# LG_TRACKER_Microcontroller.net
KiCad netlist of a schematic drawn in Altium Designer
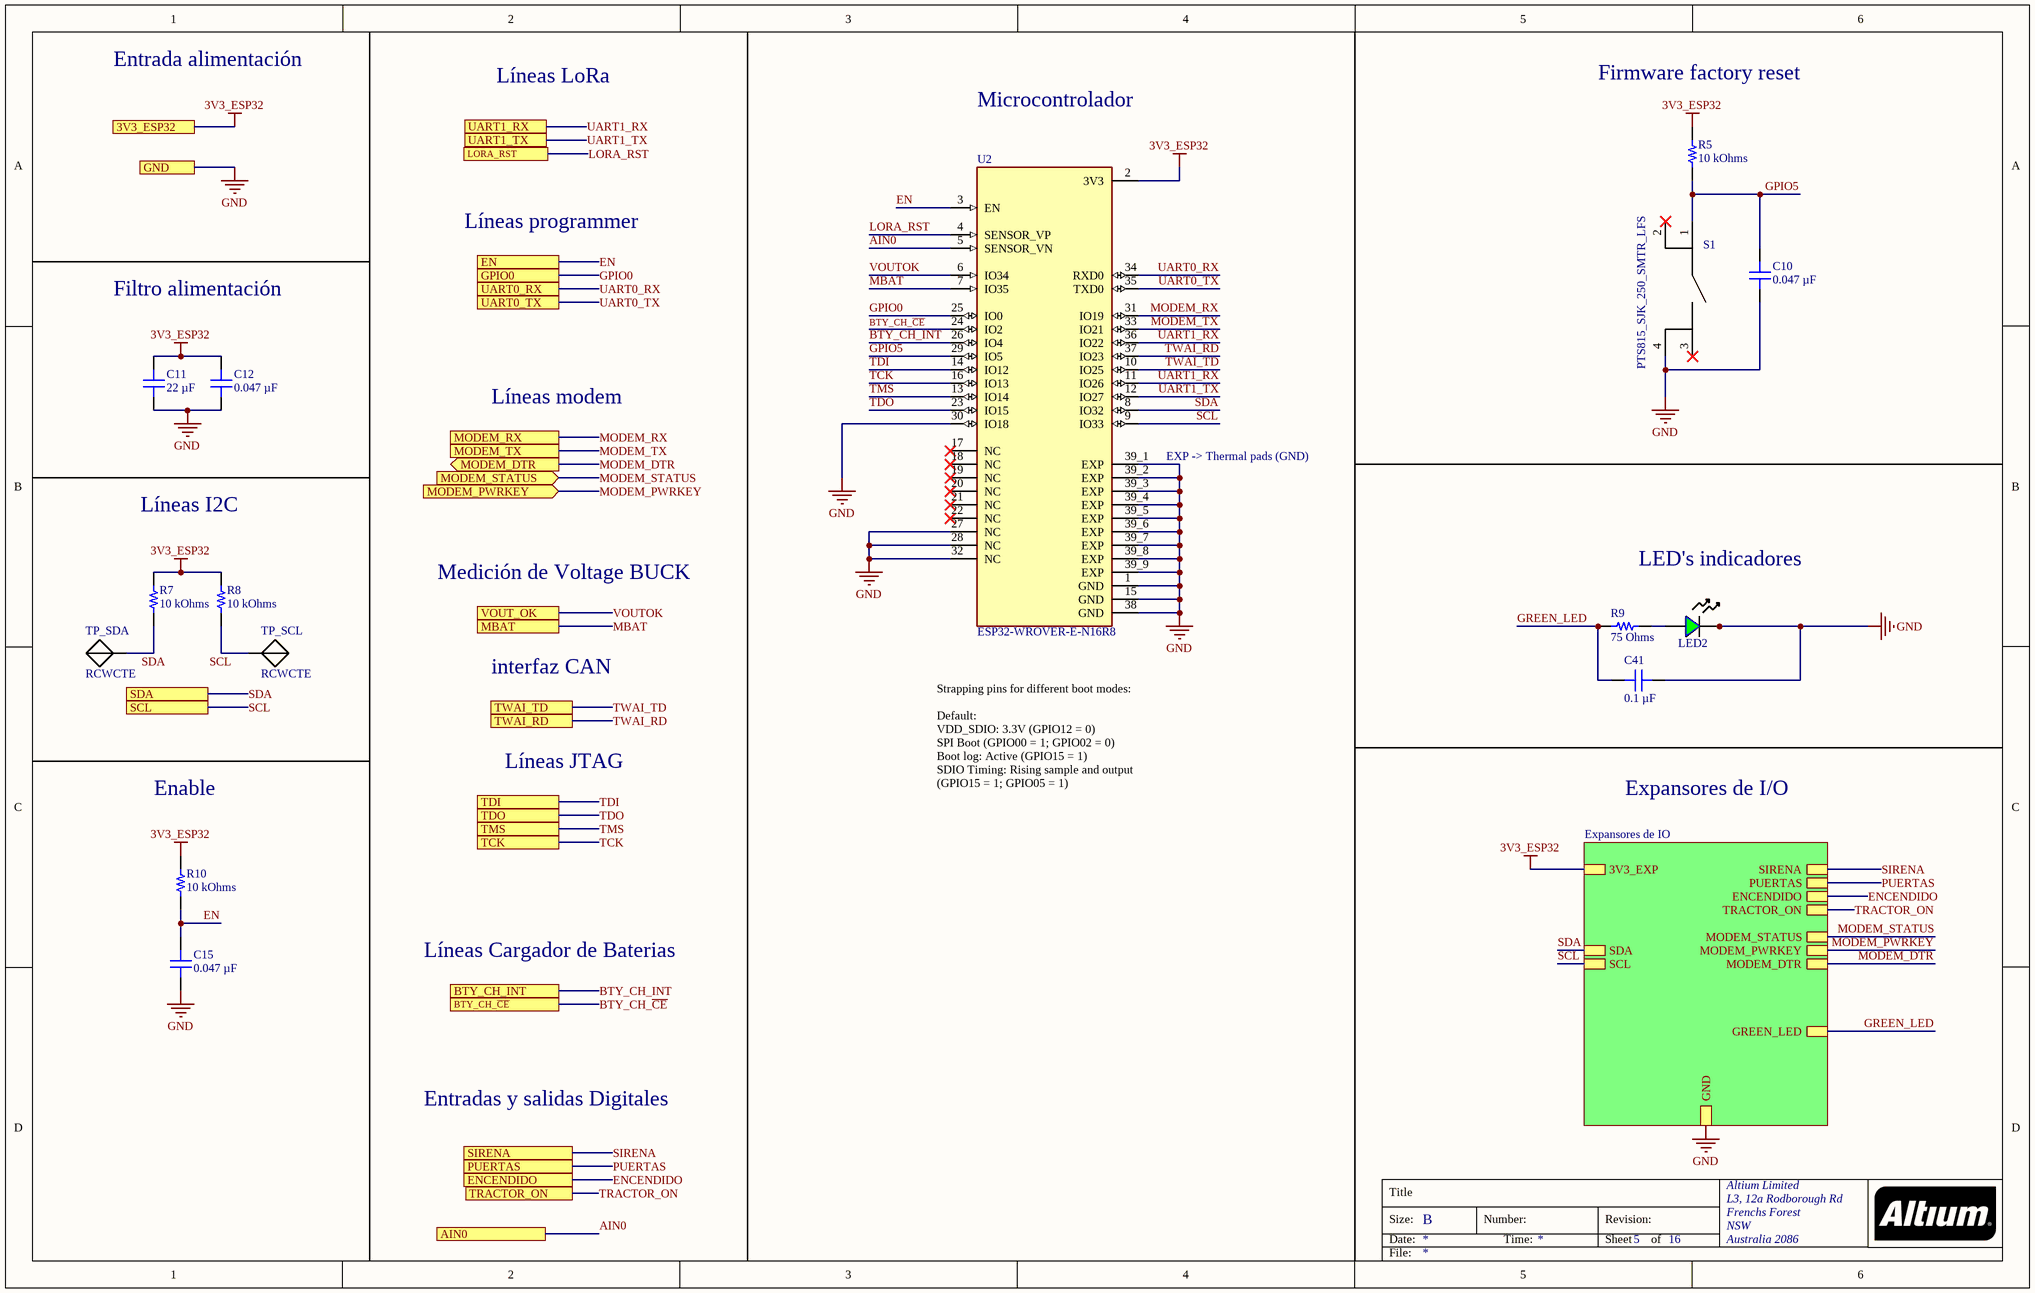
[diagram p0: LG_TRACKER_Microcontroller.SchDoc]

(export (version "E")
  (design (tool "Eeschema 10.0.6"))
  (components
    (comp (ref "C10")
      (value "0.047 µF")
      (footprint "CAP 0603_1608")
      (description "CAP CER 0.047UF 100V X7R 0603")
      (fields (field (name "PART NUMBER") "885012206118") (field (name "MANUFACTURER") "Würth Elektronik"))
      (libsource (lib "Celestial Altium Library - altium_library") (part "Capacitor"))
    )
    (comp (ref "C11")
      (value "22 µF")
      (footprint "CAP 0805_2012")
      (description "CAP CER 22UF 16V X5R 0805")
      (fields
        (field (name "PART NUMBER") "CL21A226MOCLRNC")
        (field (name "MANUFACTURER") "Samsung Electro-Mechanics")
      )
      (libsource (lib "Celestial Altium Library - altium_library") (part "Capacitor"))
    )
    (comp (ref "C12")
      (value "0.047 µF")
      (footprint "CAP 0603_1608")
      (description "CAP CER 0.047UF 100V X7R 0603")
      (fields (field (name "PART NUMBER") "885012206118") (field (name "MANUFACTURER") "Würth Elektronik"))
      (libsource (lib "Celestial Altium Library - altium_library") (part "Capacitor"))
    )
    (comp (ref "C15")
      (value "0.047 µF")
      (footprint "CAP 0603_1608")
      (description "CAP CER 0.047UF 100V X7R 0603")
      (fields (field (name "PART NUMBER") "885012206118") (field (name "MANUFACTURER") "Würth Elektronik"))
      (libsource (lib "Celestial Altium Library - altium_library") (part "Capacitor"))
    )
    (comp (ref "C41")
      (value "0.1 µF")
      (footprint "CAP 0402_1005")
      (description "CAP CER 0.1UF 50V X5R 0402")
      (fields
        (field (name "PART NUMBER") "CGA2B3X5R1H104M050BB")
        (field (name "CAPACITANCE") "0.1 µF")
        (field (name "MANUFACTURER") "TDK Corporation")
      )
      (libsource (lib "Celestial Altium Library - altium_library") (part "Capacitor"))
    )
    (comp (ref "LED2")
      (value "LTST-C170GKT")
      (footprint "0805 SMD - LED")
      (description "LED verde SMD (0805)")
      (fields (field (name "COPYRIGHT") "Copyright (C) 2023 Ultra Librarian. All rights reserved."))
      (libsource (lib "DIN_DC_Base_Board_components_SCH_footprints") (part "LTST-C170GKT"))
    )
    (comp (ref "R5")
      (value "10 kOhms")
      (footprint "RES 0603_1608")
      (description "RES 10K OHM 1% 1/10W 0603")
      (fields (field (name "PART NUMBER") "RC0603FR-0710KL") (field (name "MANUFACTURER") "Yageo"))
      (libsource (lib "Celestial Altium Library - altium_library") (part "Resistor"))
    )
    (comp (ref "R7")
      (value "10 kOhms")
      (footprint "RES 0603_1608")
      (description "RES 10K OHM 1% 1/10W 0603")
      (fields (field (name "PART NUMBER") "RC0603FR-0710KL") (field (name "MANUFACTURER") "Yageo"))
      (libsource (lib "Celestial Altium Library - altium_library") (part "Resistor"))
    )
    (comp (ref "R8")
      (value "10 kOhms")
      (footprint "RES 0603_1608")
      (description "RES 10K OHM 1% 1/10W 0603")
      (fields (field (name "PART NUMBER") "RC0603FR-0710KL") (field (name "MANUFACTURER") "Yageo"))
      (libsource (lib "Celestial Altium Library - altium_library") (part "Resistor"))
    )
    (comp (ref "R9")
      (value "75 Ohms")
      (footprint "RES 0402_1005")
      (description "RES 75 OHM 1% 1/16W 0402")
      (fields (field (name "PART NUMBER") "CRCW040275R0FKEDC") (field (name "MANUFACTURER") "Vishay Dale"))
      (libsource (lib "Celestial Altium Library - altium_library") (part "Resistor"))
    )
    (comp (ref "R10")
      (value "10 kOhms")
      (footprint "RES 0603_1608")
      (description "RES 10K OHM 1% 1/10W 0603")
      (fields (field (name "PART NUMBER") "RC0603FR-0710KL") (field (name "MANUFACTURER") "Yageo"))
      (libsource (lib "Celestial Altium Library - altium_library") (part "Resistor"))
    )
    (comp (ref "S1")
      (value "PTS815_SJK_250_SMTR_LFS")
      (footprint "PTS815SJK250SMTRLFS")
      (description "Switch")
      (fields
        (field (name "MANUFACTURER_PART_NUMBER") "PTS815 SJK 250 SMTR LFS")
        (field (name "MOUSER PART NUMBER") "611-PTS815SJK250SMTR")
      )
      (libsource (lib "DIN_DC_Base_Board_components") (part "PTS815_SJK_250_SMTR_LFS"))
    )
    (comp (ref "TP_SCL")
      (value "RCWCTE")
      (footprint "RCWCTE")
      (description "- PC Test Point - - Plating Surface Mount Mounting Type")
      (fields (field (name "MF") "KOA Speer") (field (name "DIGI-KEY_PART_NUMBER") "2019-RCWCTETR-ND"))
      (libsource (lib "DIN_DC_Base_Board_components") (part "RCWCTE"))
    )
    (comp (ref "TP_SDA")
      (value "RCWCTE")
      (footprint "RCWCTE")
      (description "- PC Test Point - - Plating Surface Mount Mounting Type")
      (fields (field (name "MF") "KOA Speer") (field (name "DIGI-KEY_PART_NUMBER") "2019-RCWCTETR-ND"))
      (libsource (lib "DIN_DC_Base_Board_components") (part "RCWCTE"))
    )
    (comp (ref "U2")
      (value "ESP32-WROVER-E-N16R8")
      (footprint "ESP32-WROVER-E-N16R8")
      (libsource (lib "DIN_DC_Base_Board_components_SCH_footprints") (part "ESP32-WROVER-E-N16R8"))
    )
  )
  (nets
    (net (code "1") (name "/AIN0") (class "Default")
      (node (ref "U2") (pin "5") (pinfunction "SENSOR_VN_5") (pintype "input"))
    )
    (net (code "2") (name "/BTY_CH_INT") (class "Default")
      (node (ref "U2") (pin "26") (pinfunction "IO4_26") (pintype "bidirectional"))
    )
    (net (code "3") (name "/BTY_CH_~{CE}") (class "Default")
      (node (ref "U2") (pin "24") (pinfunction "IO2_24") (pintype "bidirectional"))
    )
    (net (code "4") (name "/EN") (class "Default")
      (node (ref "C15") (pin "2") (pinfunction "2_2") (pintype "passive"))
      (node (ref "R10") (pin "1") (pinfunction "1_1") (pintype "passive"))
      (node (ref "U2") (pin "3") (pinfunction "EN_3") (pintype "input"))
    )
    (net (code "6") (name "/GPIO0") (class "Default")
      (node (ref "U2") (pin "25") (pinfunction "IO0_25") (pintype "bidirectional"))
    )
    (net (code "7") (name "/GPIO5") (class "Default")
      (node (ref "C10") (pin "2") (pinfunction "2_2") (pintype "passive"))
      (node (ref "R5") (pin "1") (pinfunction "1_1") (pintype "passive"))
      (node (ref "S1") (pin "1") (pinfunction "COM_1_1") (pintype "passive"))
      (node (ref "U2") (pin "29") (pinfunction "IO5_29") (pintype "bidirectional"))
    )
    (net (code "8") (name "/GREEN_LED") (class "Default")
      (node (ref "C41") (pin "2") (pinfunction "2_2") (pintype "passive"))
      (node (ref "R9") (pin "1") (pinfunction "1_1") (pintype "passive"))
    )
    (net (code "9") (name "/LORA_RST") (class "Default")
      (node (ref "U2") (pin "4") (pinfunction "SENSOR_VP_4") (pintype "input"))
    )
    (net (code "10") (name "/MBAT") (class "Default")
      (node (ref "U2") (pin "7") (pinfunction "IO35_7") (pintype "input"))
    )
    (net (code "13") (name "/MODEM_RX") (class "Default")
      (node (ref "U2") (pin "31") (pinfunction "IO19_31") (pintype "bidirectional"))
    )
    (net (code "15") (name "/MODEM_TX") (class "Default")
      (node (ref "U2") (pin "33") (pinfunction "IO21_33") (pintype "bidirectional"))
    )
    (net (code "17") (name "/SCL") (class "Default")
      (node (ref "R8") (pin "1") (pinfunction "1_1") (pintype "passive"))
      (node (ref "TP_SCL") (pin "1") (pinfunction "TP_1") (pintype "passive"))
      (node (ref "U2") (pin "9") (pinfunction "IO33_9") (pintype "bidirectional"))
    )
    (net (code "18") (name "/SDA") (class "Default")
      (node (ref "R7") (pin "1") (pinfunction "1_1") (pintype "passive"))
      (node (ref "TP_SDA") (pin "1") (pinfunction "TP_1") (pintype "passive"))
      (node (ref "U2") (pin "8") (pinfunction "IO32_8") (pintype "bidirectional"))
    )
    (net (code "20") (name "/TCK") (class "Default")
      (node (ref "U2") (pin "16") (pinfunction "IO13_16") (pintype "bidirectional"))
    )
    (net (code "21") (name "/TDI") (class "Default")
      (node (ref "U2") (pin "14") (pinfunction "IO12_14") (pintype "bidirectional"))
    )
    (net (code "22") (name "/TDO") (class "Default")
      (node (ref "U2") (pin "23") (pinfunction "IO15_23") (pintype "bidirectional"))
    )
    (net (code "23") (name "/TMS") (class "Default")
      (node (ref "U2") (pin "13") (pinfunction "IO14_13") (pintype "bidirectional"))
    )
    (net (code "25") (name "/TWAI_RD") (class "Default")
      (node (ref "U2") (pin "37") (pinfunction "IO23_37") (pintype "bidirectional"))
    )
    (net (code "26") (name "/TWAI_TD") (class "Default")
      (node (ref "U2") (pin "10") (pinfunction "IO25_10") (pintype "bidirectional"))
    )
    (net (code "27") (name "/UART0_RX") (class "Default")
      (node (ref "U2") (pin "34") (pinfunction "RXD0_34") (pintype "bidirectional"))
    )
    (net (code "28") (name "/UART0_TX") (class "Default")
      (node (ref "U2") (pin "35") (pinfunction "TXD0_35") (pintype "bidirectional"))
    )
    (net (code "29") (name "/UART1_RX") (class "Default")
      (node (ref "U2") (pin "11") (pinfunction "IO26_11") (pintype "bidirectional"))
      (node (ref "U2") (pin "36") (pinfunction "IO22_36") (pintype "bidirectional"))
    )
    (net (code "30") (name "/UART1_TX") (class "Default")
      (node (ref "U2") (pin "12") (pinfunction "IO27_12") (pintype "bidirectional"))
    )
    (net (code "31") (name "/VOUTOK") (class "Default")
      (node (ref "U2") (pin "6") (pinfunction "IO34_6") (pintype "input"))
    )
    (net (code "32") (name "3V3_ESP32") (class "Default")
      (node (ref "C11") (pin "2") (pinfunction "2_2") (pintype "passive"))
      (node (ref "C12") (pin "2") (pinfunction "2_2") (pintype "passive"))
      (node (ref "R10") (pin "2") (pinfunction "2_2") (pintype "passive"))
      (node (ref "R5") (pin "2") (pinfunction "2_2") (pintype "passive"))
      (node (ref "R7") (pin "2") (pinfunction "2_2") (pintype "passive"))
      (node (ref "R8") (pin "2") (pinfunction "2_2") (pintype "passive"))
      (node (ref "U2") (pin "2") (pinfunction "3V3_2") (pintype "power_in"))
    )
    (net (code "33") (name "GND") (class "Default")
      (node (ref "C10") (pin "1") (pinfunction "1_1") (pintype "passive"))
      (node (ref "C11") (pin "1") (pinfunction "1_1") (pintype "passive"))
      (node (ref "C12") (pin "1") (pinfunction "1_1") (pintype "passive"))
      (node (ref "C15") (pin "1") (pinfunction "1_1") (pintype "passive"))
      (node (ref "C41") (pin "1") (pinfunction "1_1") (pintype "passive"))
      (node (ref "LED2") (pin "K") (pinfunction "CATHODE_K") (pintype "passive"))
      (node (ref "S1") (pin "4") (pinfunction "N.O._2_4") (pintype "passive"))
      (node (ref "U2") (pin "1") (pinfunction "GND_1") (pintype "power_in"))
      (node (ref "U2") (pin "15") (pinfunction "GND_15") (pintype "power_in"))
      (node (ref "U2") (pin "27") (pinfunction "NC_27") (pintype "passive"))
      (node (ref "U2") (pin "28") (pinfunction "NC_28") (pintype "passive"))
      (node (ref "U2") (pin "30") (pinfunction "IO18_30") (pintype "bidirectional"))
      (node (ref "U2") (pin "32") (pinfunction "NC_32") (pintype "passive"))
      (node (ref "U2") (pin "38") (pinfunction "GND_38") (pintype "power_in"))
      (node (ref "U2") (pin "39_1") (pinfunction "EXP_39_1") (pintype "power_in"))
      (node (ref "U2") (pin "39_2") (pinfunction "EXP_39_2") (pintype "power_in"))
      (node (ref "U2") (pin "39_3") (pinfunction "EXP_39_3") (pintype "power_in"))
      (node (ref "U2") (pin "39_4") (pinfunction "EXP_39_4") (pintype "power_in"))
      (node (ref "U2") (pin "39_5") (pinfunction "EXP_39_5") (pintype "power_in"))
      (node (ref "U2") (pin "39_6") (pinfunction "EXP_39_6") (pintype "power_in"))
      (node (ref "U2") (pin "39_7") (pinfunction "EXP_39_7") (pintype "power_in"))
      (node (ref "U2") (pin "39_8") (pinfunction "EXP_39_8") (pintype "power_in"))
      (node (ref "U2") (pin "39_9") (pinfunction "EXP_39_9") (pintype "power_in"))
    )
    (net (code "34") (name "Net-(LED2-ANODE)") (class "Default")
      (node (ref "LED2") (pin "A") (pinfunction "ANODE_A") (pintype "passive"))
      (node (ref "R9") (pin "2") (pinfunction "2_2") (pintype "passive"))
    )
    (net (code "35") (name "unconnected-(S1-COM_2-Pad2)") (class "Default")
      (node (ref "S1") (pin "2") (pinfunction "COM_2_2") (pintype "passive+no_connect"))
    )
    (net (code "36") (name "unconnected-(S1-N.O._1-Pad3)") (class "Default")
      (node (ref "S1") (pin "3") (pinfunction "N.O._1_3") (pintype "passive+no_connect"))
    )
    (net (code "37") (name "unconnected-(U2-NC-Pad17)") (class "Default")
      (node (ref "U2") (pin "17") (pinfunction "NC_17") (pintype "passive+no_connect"))
    )
    (net (code "38") (name "unconnected-(U2-NC-Pad18)") (class "Default")
      (node (ref "U2") (pin "18") (pinfunction "NC_18") (pintype "passive+no_connect"))
    )
    (net (code "39") (name "unconnected-(U2-NC-Pad19)") (class "Default")
      (node (ref "U2") (pin "19") (pinfunction "NC_19") (pintype "passive+no_connect"))
    )
    (net (code "40") (name "unconnected-(U2-NC-Pad20)") (class "Default")
      (node (ref "U2") (pin "20") (pinfunction "NC_20") (pintype "passive+no_connect"))
    )
    (net (code "41") (name "unconnected-(U2-NC-Pad21)") (class "Default")
      (node (ref "U2") (pin "21") (pinfunction "NC_21") (pintype "passive+no_connect"))
    )
    (net (code "42") (name "unconnected-(U2-NC-Pad22)") (class "Default")
      (node (ref "U2") (pin "22") (pinfunction "NC_22") (pintype "passive+no_connect"))
    )
  )
)
